# M514X.net
KiCad netlist of a schematic drawn in EAGLE
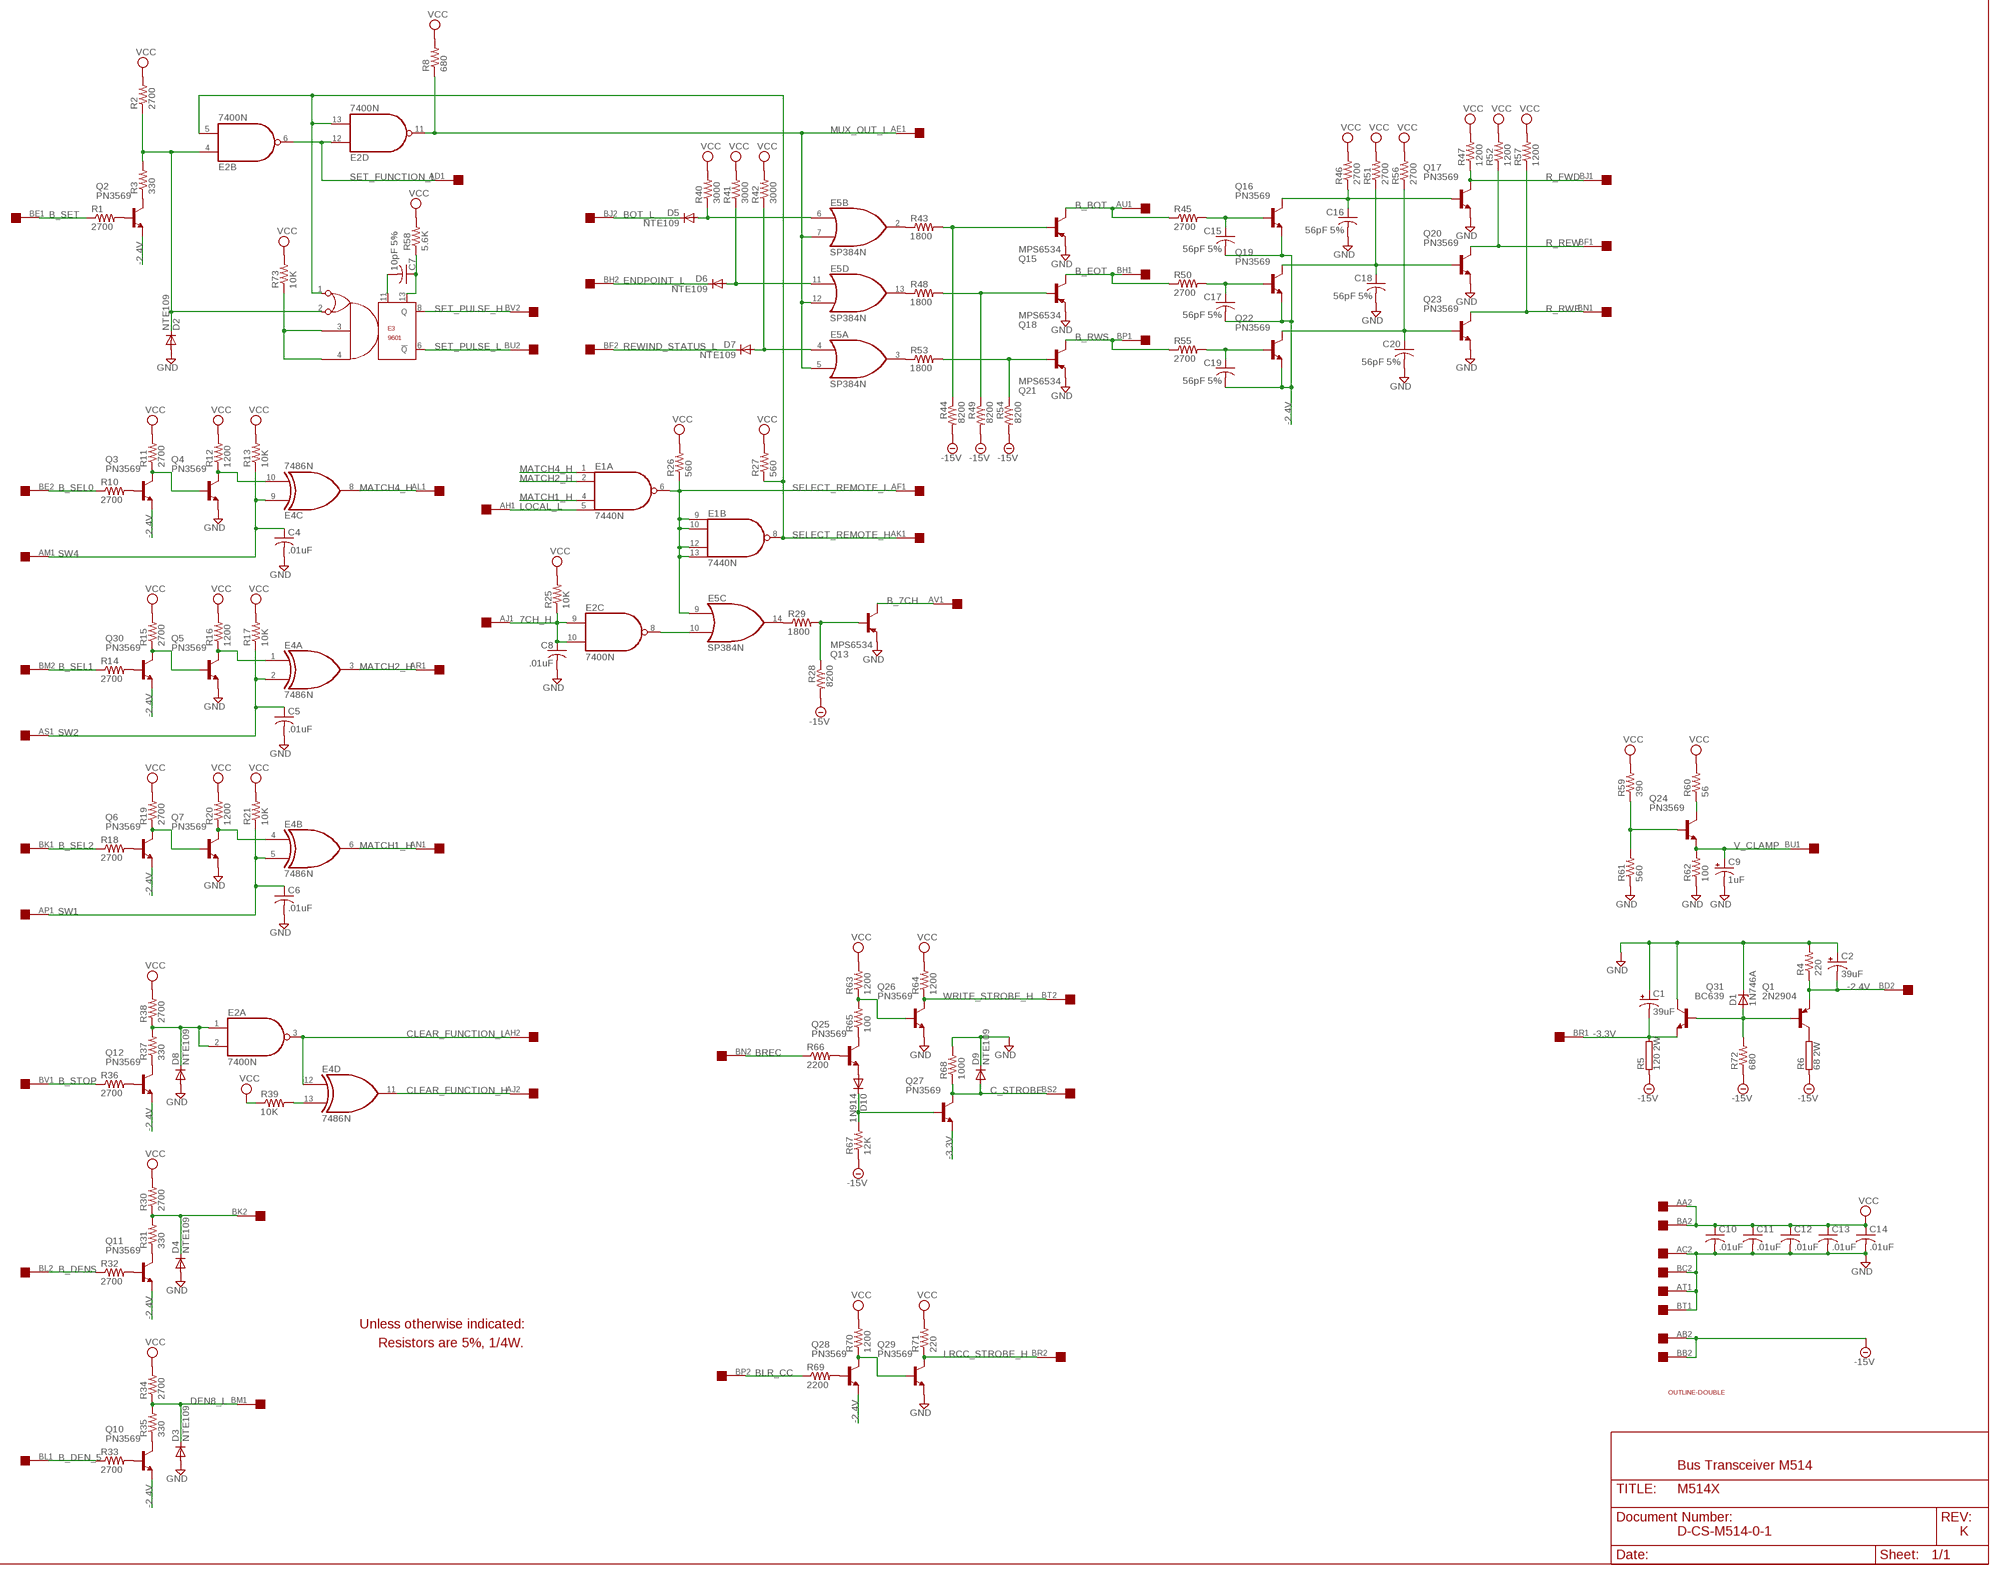
[diagram p0: schematic, sheet 1]

(export (version "E")
  (design (tool "Eeschema 10.0.6"))
  (components
    (comp (ref "C1")
      (value "39uF")
      (footprint "eagle-import:E12-8")
      (libsource (lib "eagle-import") (part "CPOL-USE20-8AXIAL"))
    )
    (comp (ref "C2")
      (value "39uF")
      (footprint "eagle-import:E12-8")
      (libsource (lib "eagle-import") (part "CPOL-USE20-8AXIAL"))
    )
    (comp (ref "C4")
      (value ".01uF")
      (footprint "eagle-import:C050-025X075")
      (libsource (lib "eagle-import") (part "C-US050-025X075"))
    )
    (comp (ref "C5")
      (value ".01uF")
      (footprint "eagle-import:C050-025X075")
      (libsource (lib "eagle-import") (part "C-US050-025X075"))
    )
    (comp (ref "C6")
      (value ".01uF")
      (footprint "eagle-import:C050-025X075")
      (libsource (lib "eagle-import") (part "C-US050-025X075"))
    )
    (comp (ref "C7")
      (value "10pF 5%")
      (footprint "eagle-import:C050-025X075")
      (libsource (lib "eagle-import") (part "C-US050-025X075"))
    )
    (comp (ref "C8")
      (value ".01uF")
      (footprint "eagle-import:C050-025X075")
      (libsource (lib "eagle-import") (part "C-US050-025X075"))
    )
    (comp (ref "C9")
      (value "1uF")
      (footprint "eagle-import:E15-5")
      (libsource (lib "eagle-import") (part "CPOL-USE15-5AXIAL"))
    )
    (comp (ref "C10")
      (value ".01uF")
      (footprint "eagle-import:C050-025X075")
      (libsource (lib "eagle-import") (part "C-US050-025X075"))
    )
    (comp (ref "C11")
      (value ".01uF")
      (footprint "eagle-import:C050-025X075")
      (libsource (lib "eagle-import") (part "C-US050-025X075"))
    )
    (comp (ref "C12")
      (value ".01uF")
      (footprint "eagle-import:C050-025X075")
      (libsource (lib "eagle-import") (part "C-US050-025X075"))
    )
    (comp (ref "C13")
      (value ".01uF")
      (footprint "eagle-import:C050-025X075")
      (libsource (lib "eagle-import") (part "C-US050-025X075"))
    )
    (comp (ref "C14")
      (value ".01uF")
      (footprint "eagle-import:C050-025X075")
      (libsource (lib "eagle-import") (part "C-US050-025X075"))
    )
    (comp (ref "C15")
      (value "56pF 5%")
      (footprint "eagle-import:C050-025X075")
      (libsource (lib "eagle-import") (part "C-US050-025X075"))
    )
    (comp (ref "C16")
      (value "56pF 5%")
      (footprint "eagle-import:C050-025X075")
      (libsource (lib "eagle-import") (part "C-US050-025X075"))
    )
    (comp (ref "C17")
      (value "56pF 5%")
      (footprint "eagle-import:C050-025X075")
      (libsource (lib "eagle-import") (part "C-US050-025X075"))
    )
    (comp (ref "C18")
      (value "56pF 5%")
      (footprint "eagle-import:C050-025X075")
      (libsource (lib "eagle-import") (part "C-US050-025X075"))
    )
    (comp (ref "C19")
      (value "56pF 5%")
      (footprint "eagle-import:C050-025X075")
      (libsource (lib "eagle-import") (part "C-US050-025X075"))
    )
    (comp (ref "C20")
      (value "56pF 5%")
      (footprint "eagle-import:C050-025X075")
      (libsource (lib "eagle-import") (part "C-US050-025X075"))
    )
    (comp (ref "D1")
      (value "1N746A")
      (footprint "eagle-import:DO35Z10")
      (libsource (lib "eagle-import") (part "ZENER-DIODEDO35Z10"))
    )
    (comp (ref "D2")
      (value "NTE109")
      (footprint "eagle-import:DO35-10")
      (libsource (lib "eagle-import") (part "1N4148DO35-10"))
    )
    (comp (ref "D3")
      (value "NTE109")
      (footprint "eagle-import:DO35-10")
      (libsource (lib "eagle-import") (part "1N4148DO35-10"))
    )
    (comp (ref "D4")
      (value "NTE109")
      (footprint "eagle-import:DO35-10")
      (libsource (lib "eagle-import") (part "1N4148DO35-10"))
    )
    (comp (ref "D5")
      (value "NTE109")
      (footprint "eagle-import:DO35-10")
      (libsource (lib "eagle-import") (part "1N4148DO35-10"))
    )
    (comp (ref "D6")
      (value "NTE109")
      (footprint "eagle-import:DO35-10")
      (libsource (lib "eagle-import") (part "1N4148DO35-10"))
    )
    (comp (ref "D7")
      (value "NTE109")
      (footprint "eagle-import:DO35-10")
      (libsource (lib "eagle-import") (part "1N4148DO35-10"))
    )
    (comp (ref "D8")
      (value "NTE109")
      (footprint "eagle-import:DO35-10")
      (libsource (lib "eagle-import") (part "1N4148DO35-10"))
    )
    (comp (ref "D9")
      (value "NTE109")
      (footprint "eagle-import:DO35-10")
      (libsource (lib "eagle-import") (part "1N4148DO35-10"))
    )
    (comp (ref "D10")
      (value "1N914")
      (footprint "eagle-import:DO35-10")
      (libsource (lib "eagle-import") (part "1N4148DO35-10"))
    )
    (comp (ref "E1")
      (value "7440N")
      (footprint "eagle-import:DIL14")
      (libsource (lib "eagle-import") (part "7420NS"))
    )
    (comp (ref "E2")
      (value "7400N")
      (footprint "eagle-import:DIL14")
      (libsource (lib "eagle-import") (part "7400N"))
    )
    (comp (ref "E3")
      (value "9601")
      (footprint "eagle-import:DIL14")
      (libsource (lib "eagle-import") (part "9601"))
    )
    (comp (ref "E4")
      (value "7486N")
      (footprint "eagle-import:DIL14")
      (libsource (lib "eagle-import") (part "7486N"))
    )
    (comp (ref "E5")
      (value "SP384N")
      (footprint "eagle-import:DIL14")
      (libsource (lib "eagle-import") (part "SP384N"))
    )
    (comp (ref "Q1")
      (value "2N2904")
      (footprint "eagle-import:TO39")
      (libsource (lib "eagle-import") (part "2N3635"))
    )
    (comp (ref "Q2")
      (value "PN3569")
      (footprint "eagle-import:TO5")
      (libsource (lib "eagle-import") (part "2N3439"))
    )
    (comp (ref "Q3")
      (value "PN3569")
      (footprint "eagle-import:TO5")
      (libsource (lib "eagle-import") (part "2N3439"))
    )
    (comp (ref "Q4")
      (value "PN3569")
      (footprint "eagle-import:TO5")
      (libsource (lib "eagle-import") (part "2N3439"))
    )
    (comp (ref "Q5")
      (value "PN3569")
      (footprint "eagle-import:TO5")
      (libsource (lib "eagle-import") (part "2N3439"))
    )
    (comp (ref "Q6")
      (value "PN3569")
      (footprint "eagle-import:TO5")
      (libsource (lib "eagle-import") (part "2N3439"))
    )
    (comp (ref "Q7")
      (value "PN3569")
      (footprint "eagle-import:TO5")
      (libsource (lib "eagle-import") (part "2N3439"))
    )
    (comp (ref "Q10")
      (value "PN3569")
      (footprint "eagle-import:TO5")
      (libsource (lib "eagle-import") (part "2N3439"))
    )
    (comp (ref "Q11")
      (value "PN3569")
      (footprint "eagle-import:TO5")
      (libsource (lib "eagle-import") (part "2N3439"))
    )
    (comp (ref "Q12")
      (value "PN3569")
      (footprint "eagle-import:TO5")
      (libsource (lib "eagle-import") (part "2N3439"))
    )
    (comp (ref "Q13")
      (value "MPS6534")
      (footprint "eagle-import:TO39")
      (libsource (lib "eagle-import") (part "2N3635"))
    )
    (comp (ref "Q15")
      (value "MPS6534")
      (footprint "eagle-import:TO39")
      (libsource (lib "eagle-import") (part "2N3635"))
    )
    (comp (ref "Q16")
      (value "PN3569")
      (footprint "eagle-import:TO5")
      (libsource (lib "eagle-import") (part "2N3439"))
    )
    (comp (ref "Q17")
      (value "PN3569")
      (footprint "eagle-import:TO5")
      (libsource (lib "eagle-import") (part "2N3439"))
    )
    (comp (ref "Q18")
      (value "MPS6534")
      (footprint "eagle-import:TO39")
      (libsource (lib "eagle-import") (part "2N3635"))
    )
    (comp (ref "Q19")
      (value "PN3569")
      (footprint "eagle-import:TO5")
      (libsource (lib "eagle-import") (part "2N3439"))
    )
    (comp (ref "Q20")
      (value "PN3569")
      (footprint "eagle-import:TO5")
      (libsource (lib "eagle-import") (part "2N3439"))
    )
    (comp (ref "Q21")
      (value "MPS6534")
      (footprint "eagle-import:TO39")
      (libsource (lib "eagle-import") (part "2N3635"))
    )
    (comp (ref "Q22")
      (value "PN3569")
      (footprint "eagle-import:TO5")
      (libsource (lib "eagle-import") (part "2N3439"))
    )
    (comp (ref "Q23")
      (value "PN3569")
      (footprint "eagle-import:TO5")
      (libsource (lib "eagle-import") (part "2N3439"))
    )
    (comp (ref "Q24")
      (value "PN3569")
      (footprint "eagle-import:TO5")
      (libsource (lib "eagle-import") (part "2N3439"))
    )
    (comp (ref "Q25")
      (value "PN3569")
      (footprint "eagle-import:TO5")
      (libsource (lib "eagle-import") (part "2N3439"))
    )
    (comp (ref "Q26")
      (value "PN3569")
      (footprint "eagle-import:TO5")
      (libsource (lib "eagle-import") (part "2N3439"))
    )
    (comp (ref "Q27")
      (value "PN3569")
      (footprint "eagle-import:TO5")
      (libsource (lib "eagle-import") (part "2N3439"))
    )
    (comp (ref "Q28")
      (value "PN3569")
      (footprint "eagle-import:TO5")
      (libsource (lib "eagle-import") (part "2N3439"))
    )
    (comp (ref "Q29")
      (value "PN3569")
      (footprint "eagle-import:TO5")
      (libsource (lib "eagle-import") (part "2N3439"))
    )
    (comp (ref "Q30")
      (value "PN3569")
      (footprint "eagle-import:TO5")
      (libsource (lib "eagle-import") (part "2N3439"))
    )
    (comp (ref "Q31")
      (value "BC639")
      (footprint "eagle-import:TO5")
      (libsource (lib "eagle-import") (part "2N3439"))
    )
    (comp (ref "R1")
      (value "2700")
      (footprint "eagle-import:0207_10")
      (libsource (lib "eagle-import") (part "R-US_0207/10"))
    )
    (comp (ref "R2")
      (value "2700")
      (footprint "eagle-import:0207_10")
      (libsource (lib "eagle-import") (part "R-US_0207/10"))
    )
    (comp (ref "R3")
      (value "330")
      (footprint "eagle-import:0207_10")
      (libsource (lib "eagle-import") (part "R-US_0207/10"))
    )
    (comp (ref "R4")
      (value "220")
      (footprint "eagle-import:0207_10")
      (libsource (lib "eagle-import") (part "R-US_0207/10"))
    )
    (comp (ref "R5")
      (value "120 2W")
      (footprint "eagle-import:KH206-8")
      (libsource (lib "eagle-import") (part "RKH206-8"))
    )
    (comp (ref "R6")
      (value "68 2W")
      (footprint "eagle-import:KH206-8")
      (libsource (lib "eagle-import") (part "RKH206-8"))
    )
    (comp (ref "R8")
      (value "680")
      (footprint "eagle-import:0207_10")
      (libsource (lib "eagle-import") (part "R-US_0207/10"))
    )
    (comp (ref "R10")
      (value "2700")
      (footprint "eagle-import:0207_10")
      (libsource (lib "eagle-import") (part "R-US_0207/10"))
    )
    (comp (ref "R11")
      (value "2700")
      (footprint "eagle-import:0207_10")
      (libsource (lib "eagle-import") (part "R-US_0207/10"))
    )
    (comp (ref "R12")
      (value "1200")
      (footprint "eagle-import:0207_10")
      (libsource (lib "eagle-import") (part "R-US_0207/10"))
    )
    (comp (ref "R13")
      (value "10K")
      (footprint "eagle-import:0207_10")
      (libsource (lib "eagle-import") (part "R-US_0207/10"))
    )
    (comp (ref "R14")
      (value "2700")
      (footprint "eagle-import:0207_10")
      (libsource (lib "eagle-import") (part "R-US_0207/10"))
    )
    (comp (ref "R15")
      (value "2700")
      (footprint "eagle-import:0207_10")
      (libsource (lib "eagle-import") (part "R-US_0207/10"))
    )
    (comp (ref "R16")
      (value "1200")
      (footprint "eagle-import:0207_10")
      (libsource (lib "eagle-import") (part "R-US_0207/10"))
    )
    (comp (ref "R17")
      (value "10K")
      (footprint "eagle-import:0207_10")
      (libsource (lib "eagle-import") (part "R-US_0207/10"))
    )
    (comp (ref "R18")
      (value "2700")
      (footprint "eagle-import:0207_10")
      (libsource (lib "eagle-import") (part "R-US_0207/10"))
    )
    (comp (ref "R19")
      (value "2700")
      (footprint "eagle-import:0207_10")
      (libsource (lib "eagle-import") (part "R-US_0207/10"))
    )
    (comp (ref "R20")
      (value "1200")
      (footprint "eagle-import:0207_10")
      (libsource (lib "eagle-import") (part "R-US_0207/10"))
    )
    (comp (ref "R21")
      (value "10K")
      (footprint "eagle-import:0207_10")
      (libsource (lib "eagle-import") (part "R-US_0207/10"))
    )
    (comp (ref "R25")
      (value "10K")
      (footprint "eagle-import:0207_10")
      (libsource (lib "eagle-import") (part "R-US_0207/10"))
    )
    (comp (ref "R26")
      (value "560")
      (footprint "eagle-import:0207_10")
      (libsource (lib "eagle-import") (part "R-US_0207/10"))
    )
    (comp (ref "R27")
      (value "560")
      (footprint "eagle-import:0207_10")
      (libsource (lib "eagle-import") (part "R-US_0207/10"))
    )
    (comp (ref "R28")
      (value "8200")
      (footprint "eagle-import:0207_10")
      (libsource (lib "eagle-import") (part "R-US_0207/10"))
    )
    (comp (ref "R29")
      (value "1800")
      (footprint "eagle-import:0207_10")
      (libsource (lib "eagle-import") (part "R-US_0207/10"))
    )
    (comp (ref "R30")
      (value "2700")
      (footprint "eagle-import:0207_10")
      (libsource (lib "eagle-import") (part "R-US_0207/10"))
    )
    (comp (ref "R31")
      (value "330")
      (footprint "eagle-import:0207_10")
      (libsource (lib "eagle-import") (part "R-US_0207/10"))
    )
    (comp (ref "R32")
      (value "2700")
      (footprint "eagle-import:0207_10")
      (libsource (lib "eagle-import") (part "R-US_0207/10"))
    )
    (comp (ref "R33")
      (value "2700")
      (footprint "eagle-import:0207_10")
      (libsource (lib "eagle-import") (part "R-US_0207/10"))
    )
    (comp (ref "R34")
      (value "2700")
      (footprint "eagle-import:0207_10")
      (libsource (lib "eagle-import") (part "R-US_0207/10"))
    )
    (comp (ref "R35")
      (value "330")
      (footprint "eagle-import:0207_10")
      (libsource (lib "eagle-import") (part "R-US_0207/10"))
    )
    (comp (ref "R36")
      (value "2700")
      (footprint "eagle-import:0207_10")
      (libsource (lib "eagle-import") (part "R-US_0207/10"))
    )
    (comp (ref "R37")
      (value "330")
      (footprint "eagle-import:0207_10")
      (libsource (lib "eagle-import") (part "R-US_0207/10"))
    )
    (comp (ref "R38")
      (value "2700")
      (footprint "eagle-import:0207_10")
      (libsource (lib "eagle-import") (part "R-US_0207/10"))
    )
    (comp (ref "R39")
      (value "10K")
      (footprint "eagle-import:0207_10")
      (libsource (lib "eagle-import") (part "R-US_0207/10"))
    )
    (comp (ref "R40")
      (value "3000")
      (footprint "eagle-import:0207_10")
      (libsource (lib "eagle-import") (part "R-US_0207/10"))
    )
    (comp (ref "R41")
      (value "3000")
      (footprint "eagle-import:0207_10")
      (libsource (lib "eagle-import") (part "R-US_0207/10"))
    )
    (comp (ref "R42")
      (value "3000")
      (footprint "eagle-import:0207_10")
      (libsource (lib "eagle-import") (part "R-US_0207/10"))
    )
    (comp (ref "R43")
      (value "1800")
      (footprint "eagle-import:0207_10")
      (libsource (lib "eagle-import") (part "R-US_0207/10"))
    )
    (comp (ref "R44")
      (value "8200")
      (footprint "eagle-import:0207_10")
      (libsource (lib "eagle-import") (part "R-US_0207/10"))
    )
    (comp (ref "R45")
      (value "2700")
      (footprint "eagle-import:0207_10")
      (libsource (lib "eagle-import") (part "R-US_0207/10"))
    )
    (comp (ref "R46")
      (value "2700")
      (footprint "eagle-import:0207_10")
      (libsource (lib "eagle-import") (part "R-US_0207/10"))
    )
    (comp (ref "R47")
      (value "1200")
      (footprint "eagle-import:0207_10")
      (libsource (lib "eagle-import") (part "R-US_0207/10"))
    )
    (comp (ref "R48")
      (value "1800")
      (footprint "eagle-import:0207_10")
      (libsource (lib "eagle-import") (part "R-US_0207/10"))
    )
    (comp (ref "R49")
      (value "8200")
      (footprint "eagle-import:0207_10")
      (libsource (lib "eagle-import") (part "R-US_0207/10"))
    )
    (comp (ref "R50")
      (value "2700")
      (footprint "eagle-import:0207_10")
      (libsource (lib "eagle-import") (part "R-US_0207/10"))
    )
    (comp (ref "R51")
      (value "2700")
      (footprint "eagle-import:0207_10")
      (libsource (lib "eagle-import") (part "R-US_0207/10"))
    )
    (comp (ref "R52")
      (value "1200")
      (footprint "eagle-import:0207_10")
      (libsource (lib "eagle-import") (part "R-US_0207/10"))
    )
    (comp (ref "R53")
      (value "1800")
      (footprint "eagle-import:0207_10")
      (libsource (lib "eagle-import") (part "R-US_0207/10"))
    )
    (comp (ref "R54")
      (value "8200")
      (footprint "eagle-import:0207_10")
      (libsource (lib "eagle-import") (part "R-US_0207/10"))
    )
    (comp (ref "R55")
      (value "2700")
      (footprint "eagle-import:0207_10")
      (libsource (lib "eagle-import") (part "R-US_0207/10"))
    )
    (comp (ref "R56")
      (value "2700")
      (footprint "eagle-import:0207_10")
      (libsource (lib "eagle-import") (part "R-US_0207/10"))
    )
    (comp (ref "R57")
      (value "1200")
      (footprint "eagle-import:0207_10")
      (libsource (lib "eagle-import") (part "R-US_0207/10"))
    )
    (comp (ref "R58")
      (value "5.6K")
      (footprint "eagle-import:0207_10")
      (libsource (lib "eagle-import") (part "R-US_0207/10"))
    )
    (comp (ref "R59")
      (value "390")
      (footprint "eagle-import:0207_10")
      (libsource (lib "eagle-import") (part "R-US_0207/10"))
    )
    (comp (ref "R60")
      (value "56")
      (footprint "eagle-import:0207_10")
      (libsource (lib "eagle-import") (part "R-US_0207/10"))
    )
    (comp (ref "R61")
      (value "560")
      (footprint "eagle-import:0207_10")
      (libsource (lib "eagle-import") (part "R-US_0207/10"))
    )
    (comp (ref "R62")
      (value "100")
      (footprint "eagle-import:0207_10")
      (libsource (lib "eagle-import") (part "R-US_0207/10"))
    )
    (comp (ref "R63")
      (value "1200")
      (footprint "eagle-import:0207_10")
      (libsource (lib "eagle-import") (part "R-US_0207/10"))
    )
    (comp (ref "R64")
      (value "1200")
      (footprint "eagle-import:0207_10")
      (libsource (lib "eagle-import") (part "R-US_0207/10"))
    )
    (comp (ref "R65")
      (value "100")
      (footprint "eagle-import:0207_10")
      (libsource (lib "eagle-import") (part "R-US_0207/10"))
    )
    (comp (ref "R66")
      (value "2200")
      (footprint "eagle-import:0207_10")
      (libsource (lib "eagle-import") (part "R-US_0207/10"))
    )
    (comp (ref "R67")
      (value "12K")
      (footprint "eagle-import:0207_10")
      (libsource (lib "eagle-import") (part "R-US_0207/10"))
    )
    (comp (ref "R68")
      (value "1000")
      (footprint "eagle-import:0207_10")
      (libsource (lib "eagle-import") (part "R-US_0207/10"))
    )
    (comp (ref "R69")
      (value "2200")
      (footprint "eagle-import:0207_10")
      (libsource (lib "eagle-import") (part "R-US_0207/10"))
    )
    (comp (ref "R70")
      (value "1200")
      (footprint "eagle-import:0207_10")
      (libsource (lib "eagle-import") (part "R-US_0207/10"))
    )
    (comp (ref "R71")
      (value "220")
      (footprint "eagle-import:0207_10")
      (libsource (lib "eagle-import") (part "R-US_0207/10"))
    )
    (comp (ref "R72")
      (value "680")
      (footprint "eagle-import:0207_10")
      (libsource (lib "eagle-import") (part "R-US_0207/10"))
    )
    (comp (ref "R73")
      (value "10K")
      (footprint "eagle-import:0207_10")
      (libsource (lib "eagle-import") (part "R-US_0207/10"))
    )
    (comp (ref "U$1")
      (value "DOUBLE")
      (footprint "eagle-import:EDGE-CON4")
      (libsource (lib "eagle-import") (part "DOUBLE"))
    )
    (comp (ref "U$2")
      (value "OUTLINE-DOUBLE")
      (footprint "eagle-import:DOUBLE")
      (libsource (lib "eagle-import") (part "OUTLINE-DOUBLE"))
    )
  )
  (nets
    (net (code "1") (name "-15V") (class "Default")
      (node (ref "R28") (pin "2") (pinfunction "2_2") (pintype "passive"))
      (node (ref "R44") (pin "2") (pinfunction "2_2") (pintype "passive"))
      (node (ref "R49") (pin "2") (pinfunction "2_2") (pintype "passive"))
      (node (ref "R5") (pin "1") (pinfunction "1_1") (pintype "passive"))
      (node (ref "R54") (pin "2") (pinfunction "2_2") (pintype "passive"))
      (node (ref "R6") (pin "1") (pinfunction "1_1") (pintype "passive"))
      (node (ref "R67") (pin "1") (pinfunction "1_1") (pintype "passive"))
      (node (ref "R72") (pin "1") (pinfunction "1_1") (pintype "passive"))
      (node (ref "U$1") (pin "AB2") (pinfunction "1_AB2") (pintype "bidirectional"))
      (node (ref "U$1") (pin "BB2") (pinfunction "1_BB2") (pintype "bidirectional"))
    )
    (net (code "2") (name "/-2.4V") (class "Default")
      (node (ref "C15") (pin "2") (pinfunction "2_2") (pintype "passive"))
      (node (ref "C17") (pin "2") (pinfunction "2_2") (pintype "passive"))
      (node (ref "C19") (pin "2") (pinfunction "2_2") (pintype "passive"))
      (node (ref "C2") (pin "-") (pinfunction "-_-") (pintype "passive"))
      (node (ref "Q1") (pin "1") (pinfunction "E_1") (pintype "passive"))
      (node (ref "Q10") (pin "1") (pinfunction "E_1") (pintype "passive"))
      (node (ref "Q11") (pin "1") (pinfunction "E_1") (pintype "passive"))
      (node (ref "Q12") (pin "1") (pinfunction "E_1") (pintype "passive"))
      (node (ref "Q16") (pin "1") (pinfunction "E_1") (pintype "passive"))
      (node (ref "Q19") (pin "1") (pinfunction "E_1") (pintype "passive"))
      (node (ref "Q2") (pin "1") (pinfunction "E_1") (pintype "passive"))
      (node (ref "Q22") (pin "1") (pinfunction "E_1") (pintype "passive"))
      (node (ref "Q28") (pin "1") (pinfunction "E_1") (pintype "passive"))
      (node (ref "Q3") (pin "1") (pinfunction "E_1") (pintype "passive"))
      (node (ref "Q30") (pin "1") (pinfunction "E_1") (pintype "passive"))
      (node (ref "Q6") (pin "1") (pinfunction "E_1") (pintype "passive"))
      (node (ref "R4") (pin "1") (pinfunction "1_1") (pintype "passive"))
      (node (ref "U$1") (pin "BD2") (pinfunction "1_BD2") (pintype "bidirectional"))
    )
    (net (code "3") (name "/-3.3V") (class "Default")
      (node (ref "C1") (pin "-") (pinfunction "-_-") (pintype "passive"))
      (node (ref "Q27") (pin "1") (pinfunction "E_1") (pintype "passive"))
      (node (ref "Q31") (pin "1") (pinfunction "E_1") (pintype "passive"))
      (node (ref "R5") (pin "2") (pinfunction "2_2") (pintype "passive"))
      (node (ref "U$1") (pin "BR1") (pinfunction "1_BR1") (pintype "bidirectional"))
    )
    (net (code "4") (name "/7CH_H") (class "Default")
      (node (ref "C8") (pin "1") (pinfunction "1_1") (pintype "passive"))
      (node (ref "E2") (pin "10") (pinfunction "I1_10") (pintype "input"))
      (node (ref "E2") (pin "9") (pinfunction "I0_9") (pintype "input"))
      (node (ref "R25") (pin "1") (pinfunction "1_1") (pintype "passive"))
      (node (ref "U$1") (pin "AJ1") (pinfunction "1_AJ1") (pintype "bidirectional"))
    )
    (net (code "5") (name "/BLR_CC") (class "Default")
      (node (ref "R69") (pin "1") (pinfunction "1_1") (pintype "passive"))
      (node (ref "U$1") (pin "BP2") (pinfunction "1_BP2") (pintype "bidirectional"))
    )
    (net (code "6") (name "/BOT_L") (class "Default")
      (node (ref "D5") (pin "C") (pinfunction "C_C") (pintype "passive"))
      (node (ref "U$1") (pin "BJ2") (pinfunction "1_BJ2") (pintype "bidirectional"))
    )
    (net (code "7") (name "/BREC") (class "Default")
      (node (ref "R66") (pin "1") (pinfunction "1_1") (pintype "passive"))
      (node (ref "U$1") (pin "BN2") (pinfunction "1_BN2") (pintype "bidirectional"))
    )
    (net (code "8") (name "/B_7CH") (class "Default")
      (node (ref "Q13") (pin "3") (pinfunction "C_3") (pintype "passive"))
      (node (ref "U$1") (pin "AV1") (pinfunction "1_AV1") (pintype "bidirectional"))
    )
    (net (code "9") (name "/B_BOT") (class "Default")
      (node (ref "Q15") (pin "3") (pinfunction "C_3") (pintype "passive"))
      (node (ref "R45") (pin "1") (pinfunction "1_1") (pintype "passive"))
      (node (ref "U$1") (pin "AU1") (pinfunction "1_AU1") (pintype "bidirectional"))
    )
    (net (code "10") (name "/B_DENS") (class "Default")
      (node (ref "R32") (pin "1") (pinfunction "1_1") (pintype "passive"))
      (node (ref "U$1") (pin "BL2") (pinfunction "1_BL2") (pintype "bidirectional"))
    )
    (net (code "11") (name "/B_DEN_5") (class "Default")
      (node (ref "R33") (pin "1") (pinfunction "1_1") (pintype "passive"))
      (node (ref "U$1") (pin "BL1") (pinfunction "1_BL1") (pintype "bidirectional"))
    )
    (net (code "12") (name "/B_EOT") (class "Default")
      (node (ref "Q18") (pin "3") (pinfunction "C_3") (pintype "passive"))
      (node (ref "R50") (pin "1") (pinfunction "1_1") (pintype "passive"))
      (node (ref "U$1") (pin "BH1") (pinfunction "1_BH1") (pintype "bidirectional"))
    )
    (net (code "13") (name "/B_RWS") (class "Default")
      (node (ref "Q21") (pin "3") (pinfunction "C_3") (pintype "passive"))
      (node (ref "R55") (pin "1") (pinfunction "1_1") (pintype "passive"))
      (node (ref "U$1") (pin "BP1") (pinfunction "1_BP1") (pintype "bidirectional"))
    )
    (net (code "14") (name "/B_SEL0") (class "Default")
      (node (ref "R10") (pin "1") (pinfunction "1_1") (pintype "passive"))
      (node (ref "U$1") (pin "BE2") (pinfunction "1_BE2") (pintype "bidirectional"))
    )
    (net (code "15") (name "/B_SEL1") (class "Default")
      (node (ref "R14") (pin "1") (pinfunction "1_1") (pintype "passive"))
      (node (ref "U$1") (pin "BM2") (pinfunction "1_BM2") (pintype "bidirectional"))
    )
    (net (code "16") (name "/B_SEL2") (class "Default")
      (node (ref "R18") (pin "1") (pinfunction "1_1") (pintype "passive"))
      (node (ref "U$1") (pin "BK1") (pinfunction "1_BK1") (pintype "bidirectional"))
    )
    (net (code "17") (name "/B_SET") (class "Default")
      (node (ref "R1") (pin "1") (pinfunction "1_1") (pintype "passive"))
      (node (ref "U$1") (pin "BE1") (pinfunction "1_BE1") (pintype "bidirectional"))
    )
    (net (code "18") (name "/B_STOP") (class "Default")
      (node (ref "R36") (pin "1") (pinfunction "1_1") (pintype "passive"))
      (node (ref "U$1") (pin "BV1") (pinfunction "1_BV1") (pintype "bidirectional"))
    )
    (net (code "19") (name "/CLEAR_FUNCTION_H") (class "Default")
      (node (ref "E4") (pin "11") (pinfunction "O_11") (pintype "output"))
      (node (ref "U$1") (pin "AJ2") (pinfunction "1_AJ2") (pintype "bidirectional"))
    )
    (net (code "20") (name "/CLEAR_FUNCTION_L") (class "Default")
      (node (ref "E2") (pin "3") (pinfunction "O_3") (pintype "output"))
      (node (ref "E4") (pin "12") (pinfunction "I0_12") (pintype "input"))
      (node (ref "U$1") (pin "AH2") (pinfunction "1_AH2") (pintype "bidirectional"))
    )
    (net (code "21") (name "/C_STROBE") (class "Default")
      (node (ref "D9") (pin "A") (pinfunction "A_A") (pintype "passive"))
      (node (ref "Q27") (pin "3") (pinfunction "C_3") (pintype "passive"))
      (node (ref "R68") (pin "1") (pinfunction "1_1") (pintype "passive"))
      (node (ref "U$1") (pin "BS2") (pinfunction "1_BS2") (pintype "bidirectional"))
    )
    (net (code "22") (name "/DEN8_L") (class "Default")
      (node (ref "D3") (pin "C") (pinfunction "C_C") (pintype "passive"))
      (node (ref "R34") (pin "1") (pinfunction "1_1") (pintype "passive"))
      (node (ref "R35") (pin "2") (pinfunction "2_2") (pintype "passive"))
      (node (ref "U$1") (pin "BM1") (pinfunction "1_BM1") (pintype "bidirectional"))
    )
    (net (code "23") (name "/ENDPOINT_L") (class "Default")
      (node (ref "D6") (pin "C") (pinfunction "C_C") (pintype "passive"))
      (node (ref "U$1") (pin "BH2") (pinfunction "1_BH2") (pintype "bidirectional"))
    )
    (net (code "24") (name "/LOCAL_L") (class "Default")
      (node (ref "E1") (pin "5") (pinfunction "I3_5") (pintype "input"))
      (node (ref "U$1") (pin "AH1") (pinfunction "1_AH1") (pintype "bidirectional"))
    )
    (net (code "25") (name "/LRCC_STROBE_H") (class "Default")
      (node (ref "Q29") (pin "3") (pinfunction "C_3") (pintype "passive"))
      (node (ref "R71") (pin "1") (pinfunction "1_1") (pintype "passive"))
      (node (ref "U$1") (pin "BR2") (pinfunction "1_BR2") (pintype "bidirectional"))
    )
    (net (code "26") (name "/MATCH1_H") (class "Default")
      (node (ref "E1") (pin "4") (pinfunction "I2_4") (pintype "input"))
      (node (ref "E4") (pin "6") (pinfunction "O_6") (pintype "output"))
      (node (ref "U$1") (pin "AN1") (pinfunction "1_AN1") (pintype "bidirectional"))
    )
    (net (code "27") (name "/MATCH2_H") (class "Default")
      (node (ref "E1") (pin "2") (pinfunction "I1_2") (pintype "input"))
      (node (ref "E4") (pin "3") (pinfunction "O_3") (pintype "output"))
      (node (ref "U$1") (pin "AR1") (pinfunction "1_AR1") (pintype "bidirectional"))
    )
    (net (code "28") (name "/MATCH4_H") (class "Default")
      (node (ref "E1") (pin "1") (pinfunction "I0_1") (pintype "input"))
      (node (ref "E4") (pin "8") (pinfunction "O_8") (pintype "output"))
      (node (ref "U$1") (pin "AL1") (pinfunction "1_AL1") (pintype "bidirectional"))
    )
    (net (code "29") (name "/MUX_OUT_L") (class "Default")
      (node (ref "E2") (pin "11") (pinfunction "O_11") (pintype "output"))
      (node (ref "E5") (pin "12") (pinfunction "I1_12") (pintype "input"))
      (node (ref "E5") (pin "5") (pinfunction "I1_5") (pintype "input"))
      (node (ref "E5") (pin "7") (pinfunction "I1_7") (pintype "input"))
      (node (ref "R8") (pin "1") (pinfunction "1_1") (pintype "passive"))
      (node (ref "U$1") (pin "AE1") (pinfunction "1_AE1") (pintype "bidirectional"))
    )
    (net (code "30") (name "/REWIND_STATUS_L") (class "Default")
      (node (ref "D7") (pin "C") (pinfunction "C_C") (pintype "passive"))
      (node (ref "U$1") (pin "BF2") (pinfunction "1_BF2") (pintype "bidirectional"))
    )
    (net (code "31") (name "/R_FWD") (class "Default")
      (node (ref "Q17") (pin "3") (pinfunction "C_3") (pintype "passive"))
      (node (ref "R47") (pin "1") (pinfunction "1_1") (pintype "passive"))
      (node (ref "U$1") (pin "BJ1") (pinfunction "1_BJ1") (pintype "bidirectional"))
    )
    (net (code "32") (name "/R_REW") (class "Default")
      (node (ref "Q20") (pin "3") (pinfunction "C_3") (pintype "passive"))
      (node (ref "R52") (pin "1") (pinfunction "1_1") (pintype "passive"))
      (node (ref "U$1") (pin "BF1") (pinfunction "1_BF1") (pintype "bidirectional"))
    )
    (net (code "33") (name "/R_RWE") (class "Default")
      (node (ref "Q23") (pin "3") (pinfunction "C_3") (pintype "passive"))
      (node (ref "R57") (pin "1") (pinfunction "1_1") (pintype "passive"))
      (node (ref "U$1") (pin "BN1") (pinfunction "1_BN1") (pintype "bidirectional"))
    )
    (net (code "34") (name "/SELECT_REMOTE_H") (class "Default")
      (node (ref "E1") (pin "8") (pinfunction "O_8") (pintype "output"))
      (node (ref "E2") (pin "13") (pinfunction "I1_13") (pintype "input"))
      (node (ref "E2") (pin "5") (pinfunction "I1_5") (pintype "input"))
      (node (ref "E3") (pin "1") (pinfunction "P$1_1") (pintype "input"))
      (node (ref "R27") (pin "1") (pinfunction "1_1") (pintype "passive"))
      (node (ref "U$1") (pin "AK1") (pinfunction "1_AK1") (pintype "bidirectional"))
    )
    (net (code "35") (name "/SELECT_REMOTE_L") (class "Default")
      (node (ref "E1") (pin "10") (pinfunction "I1_10") (pintype "input"))
      (node (ref "E1") (pin "12") (pinfunction "I2_12") (pintype "input"))
      (node (ref "E1") (pin "13") (pinfunction "I3_13") (pintype "input"))
      (node (ref "E1") (pin "6") (pinfunction "O_6") (pintype "output"))
      (node (ref "E1") (pin "9") (pinfunction "I0_9") (pintype "input"))
      (node (ref "E5") (pin "9") (pinfunction "I0_9") (pintype "input"))
      (node (ref "R26") (pin "1") (pinfunction "1_1") (pintype "passive"))
      (node (ref "U$1") (pin "AF1") (pinfunction "1_AF1") (pintype "bidirectional"))
    )
    (net (code "36") (name "/SET_FUNCTION_L") (class "Default")
      (node (ref "E2") (pin "12") (pinfunction "I0_12") (pintype "input"))
      (node (ref "E2") (pin "6") (pinfunction "O_6") (pintype "output"))
      (node (ref "U$1") (pin "AD1") (pinfunction "1_AD1") (pintype "bidirectional"))
    )
    (net (code "37") (name "/SET_PULSE_H") (class "Default")
      (node (ref "E3") (pin "8") (pinfunction "Q_8") (pintype "output"))
      (node (ref "U$1") (pin "BV2") (pinfunction "1_BV2") (pintype "bidirectional"))
    )
    (net (code "38") (name "/SET_PULSE_L") (class "Default")
      (node (ref "E3") (pin "6") (pinfunction "~{Q}_6") (pintype "output"))
      (node (ref "U$1") (pin "BU2") (pinfunction "1_BU2") (pintype "bidirectional"))
    )
    (net (code "39") (name "/SW1") (class "Default")
      (node (ref "C6") (pin "1") (pinfunction "1_1") (pintype "passive"))
      (node (ref "E4") (pin "5") (pinfunction "I1_5") (pintype "input"))
      (node (ref "R21") (pin "1") (pinfunction "1_1") (pintype "passive"))
      (node (ref "U$1") (pin "AP1") (pinfunction "1_AP1") (pintype "bidirectional"))
    )
    (net (code "40") (name "/SW2") (class "Default")
      (node (ref "C5") (pin "1") (pinfunction "1_1") (pintype "passive"))
      (node (ref "E4") (pin "2") (pinfunction "I1_2") (pintype "input"))
      (node (ref "R17") (pin "1") (pinfunction "1_1") (pintype "passive"))
      (node (ref "U$1") (pin "AS1") (pinfunction "1_AS1") (pintype "bidirectional"))
    )
    (net (code "41") (name "/SW4") (class "Default")
      (node (ref "C4") (pin "1") (pinfunction "1_1") (pintype "passive"))
      (node (ref "E4") (pin "9") (pinfunction "I0_9") (pintype "input"))
      (node (ref "R13") (pin "1") (pinfunction "1_1") (pintype "passive"))
      (node (ref "U$1") (pin "AM1") (pinfunction "1_AM1") (pintype "bidirectional"))
    )
    (net (code "42") (name "/V_CLAMP") (class "Default")
      (node (ref "C9") (pin "+") (pinfunction "+_+") (pintype "passive"))
      (node (ref "Q24") (pin "1") (pinfunction "E_1") (pintype "passive"))
      (node (ref "R62") (pin "2") (pinfunction "2_2") (pintype "passive"))
      (node (ref "U$1") (pin "BU1") (pinfunction "1_BU1") (pintype "bidirectional"))
    )
    (net (code "43") (name "/WRITE_STROBE_H") (class "Default")
      (node (ref "Q26") (pin "3") (pinfunction "C_3") (pintype "passive"))
      (node (ref "R64") (pin "1") (pinfunction "1_1") (pintype "passive"))
      (node (ref "U$1") (pin "BT2") (pinfunction "1_BT2") (pintype "bidirectional"))
    )
    (net (code "44") (name "GND") (class "Default")
      (node (ref "C1") (pin "+") (pinfunction "+_+") (pintype "passive"))
      (node (ref "C10") (pin "2") (pinfunction "2_2") (pintype "passive"))
      (node (ref "C11") (pin "2") (pinfunction "2_2") (pintype "passive"))
      (node (ref "C12") (pin "2") (pinfunction "2_2") (pintype "passive"))
      (node (ref "C13") (pin "2") (pinfunction "2_2") (pintype "passive"))
      (node (ref "C14") (pin "2") (pinfunction "2_2") (pintype "passive"))
      (node (ref "C16") (pin "2") (pinfunction "2_2") (pintype "passive"))
      (node (ref "C18") (pin "2") (pinfunction "2_2") (pintype "passive"))
      (node (ref "C2") (pin "+") (pinfunction "+_+") (pintype "passive"))
      (node (ref "C20") (pin "2") (pinfunction "2_2") (pintype "passive"))
      (node (ref "C4") (pin "2") (pinfunction "2_2") (pintype "passive"))
      (node (ref "C5") (pin "2") (pinfunction "2_2") (pintype "passive"))
      (node (ref "C6") (pin "2") (pinfunction "2_2") (pintype "passive"))
      (node (ref "C8") (pin "2") (pinfunction "2_2") (pintype "passive"))
      (node (ref "C9") (pin "-") (pinfunction "-_-") (pintype "passive"))
      (node (ref "D1") (pin "C") (pinfunction "C_C") (pintype "passive"))
      (node (ref "D2") (pin "A") (pinfunction "A_A") (pintype "passive"))
      (node (ref "D3") (pin "A") (pinfunction "A_A") (pintype "passive"))
      (node (ref "D4") (pin "A") (pinfunction "A_A") (pintype "passive"))
      (node (ref "D8") (pin "A") (pinfunction "A_A") (pintype "passive"))
      (node (ref "D9") (pin "C") (pinfunction "C_C") (pintype "passive"))
      (node (ref "Q13") (pin "1") (pinfunction "E_1") (pintype "passive"))
      (node (ref "Q15") (pin "1") (pinfunction "E_1") (pintype "passive"))
      (node (ref "Q17") (pin "1") (pinfunction "E_1") (pintype "passive"))
      (node (ref "Q18") (pin "1") (pinfunction "E_1") (pintype "passive"))
      (node (ref "Q20") (pin "1") (pinfunction "E_1") (pintype "passive"))
      (node (ref "Q21") (pin "1") (pinfunction "E_1") (pintype "passive"))
      (node (ref "Q23") (pin "1") (pinfunction "E_1") (pintype "passive"))
      (node (ref "Q26") (pin "1") (pinfunction "E_1") (pintype "passive"))
      (node (ref "Q29") (pin "1") (pinfunction "E_1") (pintype "passive"))
      (node (ref "Q31") (pin "3") (pinfunction "C_3") (pintype "passive"))
      (node (ref "Q4") (pin "1") (pinfunction "E_1") (pintype "passive"))
      (node (ref "Q5") (pin "1") (pinfunction "E_1") (pintype "passive"))
      (node (ref "Q7") (pin "1") (pinfunction "E_1") (pintype "passive"))
      (node (ref "R4") (pin "2") (pinfunction "2_2") (pintype "passive"))
      (node (ref "R61") (pin "1") (pinfunction "1_1") (pintype "passive"))
      (node (ref "R62") (pin "1") (pinfunction "1_1") (pintype "passive"))
      (node (ref "R68") (pin "2") (pinfunction "2_2") (pintype "passive"))
      (node (ref "U$1") (pin "AC2") (pinfunction "1_AC2") (pintype "bidirectional"))
      (node (ref "U$1") (pin "AT1") (pinfunction "1_AT1") (pintype "bidirectional"))
      (node (ref "U$1") (pin "BC2") (pinfunction "1_BC2") (pintype "bidirectional"))
      (node (ref "U$1") (pin "BT1") (pinfunction "1_BT1") (pintype "bidirectional"))
    )
    (net (code "45") (name "Net-(E2A-I0)") (class "Default")
      (node (ref "D8") (pin "C") (pinfunction "C_C") (pintype "passive"))
      (node (ref "E2") (pin "1") (pinfunction "I0_1") (pintype "input"))
      (node (ref "E2") (pin "2") (pinfunction "I1_2") (pintype "input"))
      (node (ref "R37") (pin "2") (pinfunction "2_2") (pintype "passive"))
      (node (ref "R38") (pin "1") (pinfunction "1_1") (pintype "passive"))
    )
    (net (code "46") (name "Net-(E2B-I0)") (class "Default")
      (node (ref "D2") (pin "C") (pinfunction "C_C") (pintype "passive"))
      (node (ref "E2") (pin "4") (pinfunction "I0_4") (pintype "input"))
      (node (ref "E3") (pin "2") (pinfunction "P$2_2") (pintype "input"))
      (node (ref "R2") (pin "1") (pinfunction "1_1") (pintype "passive"))
      (node (ref "R3") (pin "2") (pinfunction "2_2") (pintype "passive"))
    )
    (net (code "47") (name "Net-(E2C-O)") (class "Default")
      (node (ref "E2") (pin "8") (pinfunction "O_8") (pintype "output"))
      (node (ref "E5") (pin "10") (pinfunction "I1_10") (pintype "input"))
    )
    (net (code "48") (name "Net-(E3A-P$3)") (class "Default")
      (node (ref "E3") (pin "3") (pinfunction "P$3_3") (pintype "input"))
      (node (ref "E3") (pin "4") (pinfunction "P$4_4") (pintype "input"))
      (node (ref "R73") (pin "1") (pinfunction "1_1") (pintype "passive"))
    )
    (net (code "49") (name "Net-(E3A-P$5)") (class "Default")
      (node (ref "C7") (pin "2") (pinfunction "2_2") (pintype "passive"))
      (node (ref "E3") (pin "11") (pinfunction "P$5_11") (pintype "bidirectional"))
    )
    (net (code "50") (name "Net-(E3A-P$6)") (class "Default")
      (node (ref "C7") (pin "1") (pinfunction "1_1") (pintype "passive"))
      (node (ref "E3") (pin "13") (pinfunction "P$6_13") (pintype "bidirectional"))
      (node (ref "R58") (pin "1") (pinfunction "1_1") (pintype "passive"))
    )
    (net (code "51") (name "Net-(E4A-I0)") (class "Default")
      (node (ref "E4") (pin "1") (pinfunction "I0_1") (pintype "input"))
      (node (ref "Q5") (pin "3") (pinfunction "C_3") (pintype "passive"))
      (node (ref "R16") (pin "1") (pinfunction "1_1") (pintype "passive"))
    )
    (net (code "52") (name "Net-(E4B-I0)") (class "Default")
      (node (ref "E4") (pin "4") (pinfunction "I0_4") (pintype "input"))
      (node (ref "Q7") (pin "3") (pinfunction "C_3") (pintype "passive"))
      (node (ref "R20") (pin "1") (pinfunction "1_1") (pintype "passive"))
    )
    (net (code "53") (name "Net-(E4C-I1)") (class "Default")
      (node (ref "E4") (pin "10") (pinfunction "I1_10") (pintype "input"))
      (node (ref "Q4") (pin "3") (pinfunction "C_3") (pintype "passive"))
      (node (ref "R12") (pin "1") (pinfunction "1_1") (pintype "passive"))
    )
    (net (code "54") (name "Net-(E4D-I1)") (class "Default")
      (node (ref "E4") (pin "13") (pinfunction "I1_13") (pintype "input"))
      (node (ref "R39") (pin "2") (pinfunction "2_2") (pintype "passive"))
    )
    (net (code "55") (name "Net-(E5A-I0)") (class "Default")
      (node (ref "D7") (pin "A") (pinfunction "A_A") (pintype "passive"))
      (node (ref "E5") (pin "4") (pinfunction "I0_4") (pintype "input"))
      (node (ref "R42") (pin "1") (pinfunction "1_1") (pintype "passive"))
    )
    (net (code "56") (name "Net-(E5A-O)") (class "Default")
      (node (ref "E5") (pin "3") (pinfunction "O_3") (pintype "output"))
      (node (ref "R53") (pin "1") (pinfunction "1_1") (pintype "passive"))
    )
    (net (code "57") (name "Net-(E5B-I0)") (class "Default")
      (node (ref "D5") (pin "A") (pinfunction "A_A") (pintype "passive"))
      (node (ref "E5") (pin "6") (pinfunction "I0_6") (pintype "input"))
      (node (ref "R40") (pin "1") (pinfunction "1_1") (pintype "passive"))
    )
    (net (code "58") (name "Net-(E5B-O)") (class "Default")
      (node (ref "E5") (pin "2") (pinfunction "O_2") (pintype "output"))
      (node (ref "R43") (pin "1") (pinfunction "1_1") (pintype "passive"))
    )
    (net (code "59") (name "Net-(E5C-O)") (class "Default")
      (node (ref "E5") (pin "14") (pinfunction "O_14") (pintype "output"))
      (node (ref "R29") (pin "1") (pinfunction "1_1") (pintype "passive"))
    )
    (net (code "60") (name "Net-(E5D-I0)") (class "Default")
      (node (ref "D6") (pin "A") (pinfunction "A_A") (pintype "passive"))
      (node (ref "E5") (pin "11") (pinfunction "I0_11") (pintype "input"))
      (node (ref "R41") (pin "1") (pinfunction "1_1") (pintype "passive"))
    )
    (net (code "61") (name "Net-(E5D-O)") (class "Default")
      (node (ref "E5") (pin "13") (pinfunction "O_13") (pintype "output"))
      (node (ref "R48") (pin "1") (pinfunction "1_1") (pintype "passive"))
    )
    (net (code "62") (name "Net-(Q1-B)") (class "Default")
      (node (ref "D1") (pin "A") (pinfunction "A_A") (pintype "passive"))
      (node (ref "Q1") (pin "2") (pinfunction "B_2") (pintype "passive"))
      (node (ref "Q31") (pin "2") (pinfunction "B_2") (pintype "passive"))
      (node (ref "R72") (pin "2") (pinfunction "2_2") (pintype "passive"))
    )
    (net (code "63") (name "Net-(Q1-C)") (class "Default")
      (node (ref "Q1") (pin "3") (pinfunction "C_3") (pintype "passive"))
      (node (ref "R6") (pin "2") (pinfunction "2_2") (pintype "passive"))
    )
    (net (code "64") (name "Net-(Q2-B)") (class "Default")
      (node (ref "Q2") (pin "2") (pinfunction "B_2") (pintype "passive"))
      (node (ref "R1") (pin "2") (pinfunction "2_2") (pintype "passive"))
    )
    (net (code "65") (name "Net-(Q2-C)") (class "Default")
      (node (ref "Q2") (pin "3") (pinfunction "C_3") (pintype "passive"))
      (node (ref "R3") (pin "1") (pinfunction "1_1") (pintype "passive"))
    )
    (net (code "66") (name "Net-(Q3-B)") (class "Default")
      (node (ref "Q3") (pin "2") (pinfunction "B_2") (pintype "passive"))
      (node (ref "R10") (pin "2") (pinfunction "2_2") (pintype "passive"))
    )
    (net (code "67") (name "Net-(Q3-C)") (class "Default")
      (node (ref "Q3") (pin "3") (pinfunction "C_3") (pintype "passive"))
      (node (ref "Q4") (pin "2") (pinfunction "B_2") (pintype "passive"))
      (node (ref "R11") (pin "1") (pinfunction "1_1") (pintype "passive"))
    )
    (net (code "68") (name "Net-(Q6-B)") (class "Default")
      (node (ref "Q6") (pin "2") (pinfunction "B_2") (pintype "passive"))
      (node (ref "R18") (pin "2") (pinfunction "2_2") (pintype "passive"))
    )
    (net (code "69") (name "Net-(Q6-C)") (class "Default")
      (node (ref "Q6") (pin "3") (pinfunction "C_3") (pintype "passive"))
      (node (ref "Q7") (pin "2") (pinfunction "B_2") (pintype "passive"))
      (node (ref "R19") (pin "1") (pinfunction "1_1") (pintype "passive"))
    )
    (net (code "70") (name "Net-(Q10-B)") (class "Default")
      (node (ref "Q10") (pin "2") (pinfunction "B_2") (pintype "passive"))
      (node (ref "R33") (pin "2") (pinfunction "2_2") (pintype "passive"))
    )
    (net (code "71") (name "Net-(Q10-C)") (class "Default")
      (node (ref "Q10") (pin "3") (pinfunction "C_3") (pintype "passive"))
      (node (ref "R35") (pin "1") (pinfunction "1_1") (pintype "passive"))
    )
    (net (code "72") (name "Net-(Q11-B)") (class "Default")
      (node (ref "Q11") (pin "2") (pinfunction "B_2") (pintype "passive"))
      (node (ref "R32") (pin "2") (pinfunction "2_2") (pintype "passive"))
    )
    (net (code "73") (name "Net-(Q11-C)") (class "Default")
      (node (ref "Q11") (pin "3") (pinfunction "C_3") (pintype "passive"))
      (node (ref "R31") (pin "1") (pinfunction "1_1") (pintype "passive"))
    )
    (net (code "74") (name "Net-(Q12-B)") (class "Default")
      (node (ref "Q12") (pin "2") (pinfunction "B_2") (pintype "passive"))
      (node (ref "R36") (pin "2") (pinfunction "2_2") (pintype "passive"))
    )
    (net (code "75") (name "Net-(Q12-C)") (class "Default")
      (node (ref "Q12") (pin "3") (pinfunction "C_3") (pintype "passive"))
      (node (ref "R37") (pin "1") (pinfunction "1_1") (pintype "passive"))
    )
    (net (code "76") (name "Net-(Q13-B)") (class "Default")
      (node (ref "Q13") (pin "2") (pinfunction "B_2") (pintype "passive"))
      (node (ref "R28") (pin "1") (pinfunction "1_1") (pintype "passive"))
      (node (ref "R29") (pin "2") (pinfunction "2_2") (pintype "passive"))
    )
    (net (code "77") (name "Net-(Q15-B)") (class "Default")
      (node (ref "Q15") (pin "2") (pinfunction "B_2") (pintype "passive"))
      (node (ref "R43") (pin "2") (pinfunction "2_2") (pintype "passive"))
      (node (ref "R44") (pin "1") (pinfunction "1_1") (pintype "passive"))
    )
    (net (code "78") (name "Net-(Q16-B)") (class "Default")
      (node (ref "C15") (pin "1") (pinfunction "1_1") (pintype "passive"))
      (node (ref "Q16") (pin "2") (pinfunction "B_2") (pintype "passive"))
      (node (ref "R45") (pin "2") (pinfunction "2_2") (pintype "passive"))
    )
    (net (code "79") (name "Net-(Q16-C)") (class "Default")
      (node (ref "C16") (pin "1") (pinfunction "1_1") (pintype "passive"))
      (node (ref "Q16") (pin "3") (pinfunction "C_3") (pintype "passive"))
      (node (ref "Q17") (pin "2") (pinfunction "B_2") (pintype "passive"))
      (node (ref "R46") (pin "1") (pinfunction "1_1") (pintype "passive"))
    )
    (net (code "80") (name "Net-(Q18-B)") (class "Default")
      (node (ref "Q18") (pin "2") (pinfunction "B_2") (pintype "passive"))
      (node (ref "R48") (pin "2") (pinfunction "2_2") (pintype "passive"))
      (node (ref "R49") (pin "1") (pinfunction "1_1") (pintype "passive"))
    )
    (net (code "81") (name "Net-(Q19-B)") (class "Default")
      (node (ref "C17") (pin "1") (pinfunction "1_1") (pintype "passive"))
      (node (ref "Q19") (pin "2") (pinfunction "B_2") (pintype "passive"))
      (node (ref "R50") (pin "2") (pinfunction "2_2") (pintype "passive"))
    )
    (net (code "82") (name "Net-(Q19-C)") (class "Default")
      (node (ref "C18") (pin "1") (pinfunction "1_1") (pintype "passive"))
      (node (ref "Q19") (pin "3") (pinfunction "C_3") (pintype "passive"))
      (node (ref "Q20") (pin "2") (pinfunction "B_2") (pintype "passive"))
      (node (ref "R51") (pin "1") (pinfunction "1_1") (pintype "passive"))
    )
    (net (code "83") (name "Net-(Q21-B)") (class "Default")
      (node (ref "Q21") (pin "2") (pinfunction "B_2") (pintype "passive"))
      (node (ref "R53") (pin "2") (pinfunction "2_2") (pintype "passive"))
      (node (ref "R54") (pin "1") (pinfunction "1_1") (pintype "passive"))
    )
    (net (code "84") (name "Net-(Q22-B)") (class "Default")
      (node (ref "C19") (pin "1") (pinfunction "1_1") (pintype "passive"))
      (node (ref "Q22") (pin "2") (pinfunction "B_2") (pintype "passive"))
      (node (ref "R55") (pin "2") (pinfunction "2_2") (pintype "passive"))
    )
    (net (code "85") (name "Net-(Q22-C)") (class "Default")
      (node (ref "C20") (pin "1") (pinfunction "1_1") (pintype "passive"))
      (node (ref "Q22") (pin "3") (pinfunction "C_3") (pintype "passive"))
      (node (ref "Q23") (pin "2") (pinfunction "B_2") (pintype "passive"))
      (node (ref "R56") (pin "1") (pinfunction "1_1") (pintype "passive"))
    )
    (net (code "86") (name "Net-(Q24-B)") (class "Default")
      (node (ref "Q24") (pin "2") (pinfunction "B_2") (pintype "passive"))
      (node (ref "R59") (pin "1") (pinfunction "1_1") (pintype "passive"))
      (node (ref "R61") (pin "2") (pinfunction "2_2") (pintype "passive"))
    )
    (net (code "87") (name "Net-(Q24-C)") (class "Default")
      (node (ref "Q24") (pin "3") (pinfunction "C_3") (pintype "passive"))
      (node (ref "R60") (pin "1") (pinfunction "1_1") (pintype "passive"))
    )
    (net (code "88") (name "Net-(Q25-B)") (class "Default")
      (node (ref "Q25") (pin "2") (pinfunction "B_2") (pintype "passive"))
      (node (ref "R66") (pin "2") (pinfunction "2_2") (pintype "passive"))
    )
    (net (code "89") (name "Net-(Q25-C)") (class "Default")
      (node (ref "Q25") (pin "3") (pinfunction "C_3") (pintype "passive"))
      (node (ref "R65") (pin "1") (pinfunction "1_1") (pintype "passive"))
    )
    (net (code "90") (name "Net-(Q25-E)") (class "Default")
      (node (ref "D10") (pin "A") (pinfunction "A_A") (pintype "passive"))
      (node (ref "Q25") (pin "1") (pinfunction "E_1") (pintype "passive"))
    )
    (net (code "91") (name "Net-(Q26-B)") (class "Default")
      (node (ref "Q26") (pin "2") (pinfunction "B_2") (pintype "passive"))
      (node (ref "R63") (pin "1") (pinfunction "1_1") (pintype "passive"))
      (node (ref "R65") (pin "2") (pinfunction "2_2") (pintype "passive"))
    )
    (net (code "92") (name "Net-(Q27-B)") (class "Default")
      (node (ref "D10") (pin "C") (pinfunction "C_C") (pintype "passive"))
      (node (ref "Q27") (pin "2") (pinfunction "B_2") (pintype "passive"))
      (node (ref "R67") (pin "2") (pinfunction "2_2") (pintype "passive"))
    )
    (net (code "93") (name "Net-(Q28-B)") (class "Default")
      (node (ref "Q28") (pin "2") (pinfunction "B_2") (pintype "passive"))
      (node (ref "R69") (pin "2") (pinfunction "2_2") (pintype "passive"))
    )
    (net (code "94") (name "Net-(Q28-C)") (class "Default")
      (node (ref "Q28") (pin "3") (pinfunction "C_3") (pintype "passive"))
      (node (ref "Q29") (pin "2") (pinfunction "B_2") (pintype "passive"))
      (node (ref "R70") (pin "1") (pinfunction "1_1") (pintype "passive"))
    )
    (net (code "95") (name "Net-(Q30-B)") (class "Default")
      (node (ref "Q30") (pin "2") (pinfunction "B_2") (pintype "passive"))
      (node (ref "R14") (pin "2") (pinfunction "2_2") (pintype "passive"))
    )
    (net (code "96") (name "Net-(Q30-C)") (class "Default")
      (node (ref "Q30") (pin "3") (pinfunction "C_3") (pintype "passive"))
      (node (ref "Q5") (pin "2") (pinfunction "B_2") (pintype "passive"))
      (node (ref "R15") (pin "1") (pinfunction "1_1") (pintype "passive"))
    )
    (net (code "97") (name "Net-(U$1BB-1)") (class "Default")
      (node (ref "D4") (pin "C") (pinfunction "C_C") (pintype "passive"))
      (node (ref "R30") (pin "1") (pinfunction "1_1") (pintype "passive"))
      (node (ref "R31") (pin "2") (pinfunction "2_2") (pintype "passive"))
      (node (ref "U$1") (pin "BK2") (pinfunction "1_BK2") (pintype "bidirectional"))
    )
    (net (code "98") (name "VCC") (class "Default")
      (node (ref "C10") (pin "1") (pinfunction "1_1") (pintype "passive"))
      (node (ref "C11") (pin "1") (pinfunction "1_1") (pintype "passive"))
      (node (ref "C12") (pin "1") (pinfunction "1_1") (pintype "passive"))
      (node (ref "C13") (pin "1") (pinfunction "1_1") (pintype "passive"))
      (node (ref "C14") (pin "1") (pinfunction "1_1") (pintype "passive"))
      (node (ref "R11") (pin "2") (pinfunction "2_2") (pintype "passive"))
      (node (ref "R12") (pin "2") (pinfunction "2_2") (pintype "passive"))
      (node (ref "R13") (pin "2") (pinfunction "2_2") (pintype "passive"))
      (node (ref "R15") (pin "2") (pinfunction "2_2") (pintype "passive"))
      (node (ref "R16") (pin "2") (pinfunction "2_2") (pintype "passive"))
      (node (ref "R17") (pin "2") (pinfunction "2_2") (pintype "passive"))
      (node (ref "R19") (pin "2") (pinfunction "2_2") (pintype "passive"))
      (node (ref "R2") (pin "2") (pinfunction "2_2") (pintype "passive"))
      (node (ref "R20") (pin "2") (pinfunction "2_2") (pintype "passive"))
      (node (ref "R21") (pin "2") (pinfunction "2_2") (pintype "passive"))
      (node (ref "R25") (pin "2") (pinfunction "2_2") (pintype "passive"))
      (node (ref "R26") (pin "2") (pinfunction "2_2") (pintype "passive"))
      (node (ref "R27") (pin "2") (pinfunction "2_2") (pintype "passive"))
      (node (ref "R30") (pin "2") (pinfunction "2_2") (pintype "passive"))
      (node (ref "R34") (pin "2") (pinfunction "2_2") (pintype "passive"))
      (node (ref "R38") (pin "2") (pinfunction "2_2") (pintype "passive"))
      (node (ref "R39") (pin "1") (pinfunction "1_1") (pintype "passive"))
      (node (ref "R40") (pin "2") (pinfunction "2_2") (pintype "passive"))
      (node (ref "R41") (pin "2") (pinfunction "2_2") (pintype "passive"))
      (node (ref "R42") (pin "2") (pinfunction "2_2") (pintype "passive"))
      (node (ref "R46") (pin "2") (pinfunction "2_2") (pintype "passive"))
      (node (ref "R47") (pin "2") (pinfunction "2_2") (pintype "passive"))
      (node (ref "R51") (pin "2") (pinfunction "2_2") (pintype "passive"))
      (node (ref "R52") (pin "2") (pinfunction "2_2") (pintype "passive"))
      (node (ref "R56") (pin "2") (pinfunction "2_2") (pintype "passive"))
      (node (ref "R57") (pin "2") (pinfunction "2_2") (pintype "passive"))
      (node (ref "R58") (pin "2") (pinfunction "2_2") (pintype "passive"))
      (node (ref "R59") (pin "2") (pinfunction "2_2") (pintype "passive"))
      (node (ref "R60") (pin "2") (pinfunction "2_2") (pintype "passive"))
      (node (ref "R63") (pin "2") (pinfunction "2_2") (pintype "passive"))
      (node (ref "R64") (pin "2") (pinfunction "2_2") (pintype "passive"))
      (node (ref "R70") (pin "2") (pinfunction "2_2") (pintype "passive"))
      (node (ref "R71") (pin "2") (pinfunction "2_2") (pintype "passive"))
      (node (ref "R73") (pin "2") (pinfunction "2_2") (pintype "passive"))
      (node (ref "R8") (pin "2") (pinfunction "2_2") (pintype "passive"))
      (node (ref "U$1") (pin "AA2") (pinfunction "1_AA2") (pintype "bidirectional"))
      (node (ref "U$1") (pin "BA2") (pinfunction "1_BA2") (pintype "bidirectional"))
    )
  )
)
